# AMU-S08-V00-IDCloops.net
KiCad netlist of a schematic drawn in Altium Designer
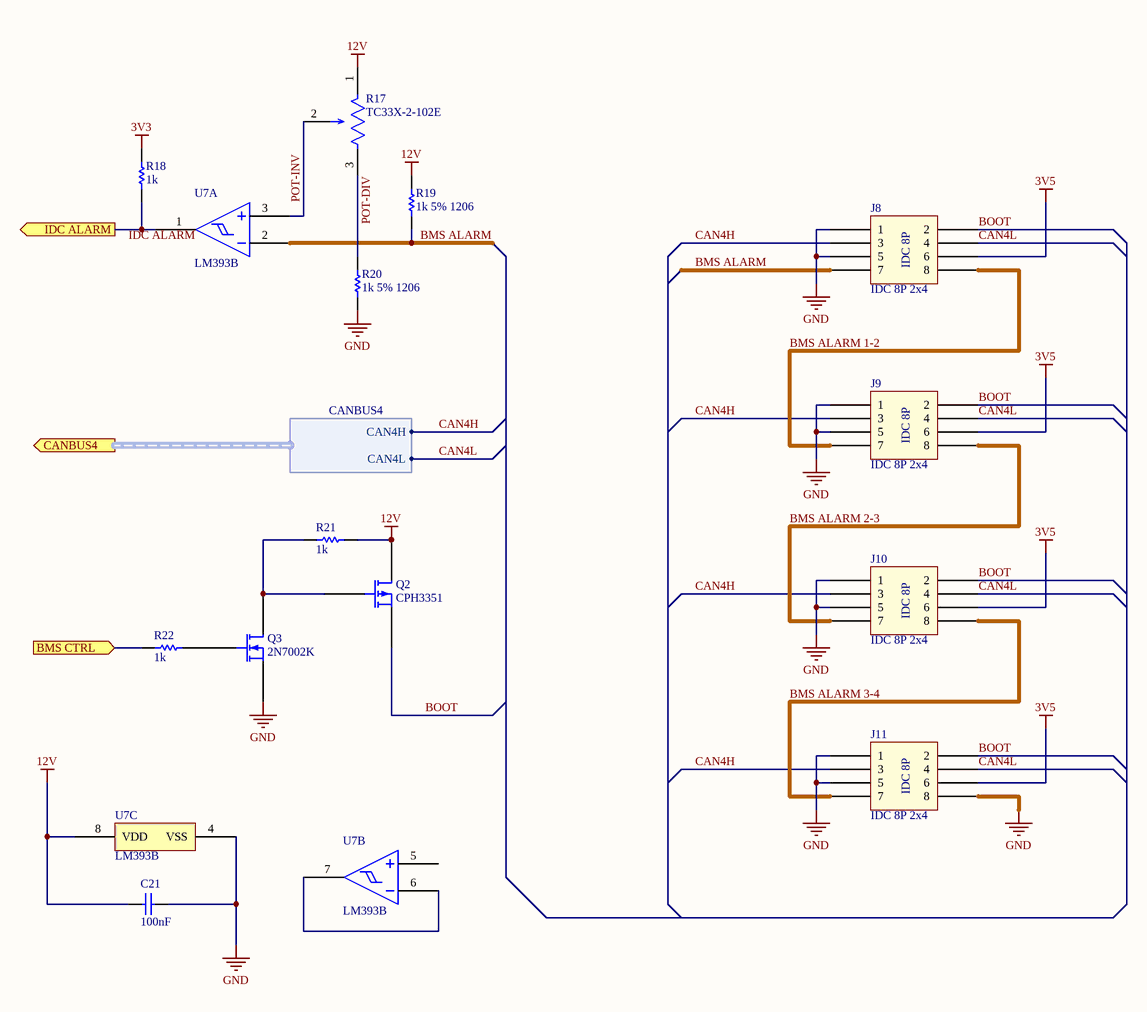
[diagram p0: AMU-S08-V00-IDCloops.SchDoc]

(export (version "E")
  (design (tool "Eeschema 10.0.6"))
  (components
    (comp (ref "C21")
      (value "100nF")
      (footprint "Cap_Ceramic_0603")
      (description "Capacitor, Ceramic, SMD, 100nF, 50V, 5%, X7R, 0603")
      (libsource (lib "StandardCapacitors") (part "100nF 50V 5% X7R 0603"))
    )
    (comp (ref "J8")
      (value "IDC 8P 2x4")
      (footprint "IDC 2.54MM 8P")
      (libsource (lib "IDCConnectors") (part "IDC 8P 2x4"))
    )
    (comp (ref "J9")
      (value "IDC 8P 2x4")
      (footprint "IDC 2.54MM 8P")
      (libsource (lib "IDCConnectors") (part "IDC 8P 2x4"))
    )
    (comp (ref "J10")
      (value "IDC 8P 2x4")
      (footprint "IDC 2.54MM 8P")
      (libsource (lib "IDCConnectors") (part "IDC 8P 2x4"))
    )
    (comp (ref "J11")
      (value "IDC 8P 2x4")
      (footprint "IDC 2.54MM 8P")
      (libsource (lib "IDCConnectors") (part "IDC 8P 2x4"))
    )
    (comp (ref "Q2")
      (value "CPH3351")
      (footprint "SOT-23-3")
      (description "P-Channel 60V 1.8A (Ta) 1W (Ta) Surface Mount 3-CPH")
      (libsource (lib "QUTMS_Transistors") (part "CPH3351"))
    )
    (comp (ref "Q3")
      (value "2N7002K")
      (footprint "SOT-23-3")
      (description "N-Channel 60V 300mA (Ta) 350mW (Ta) Surface Mount SOT-23 (TO-236AB)")
      (libsource (lib "QUTMS_Transistors") (part "2N7002K"))
    )
    (comp (ref "R17")
      (value "TC33X-2-102E")
      (footprint "TC33")
      (description "1 kOhms 0.1W, 1/10W J Lead Surface Mount Trimmer Potentiometer Cermet 1 Turn Top Adjustment")
      (libsource (lib "QUTMS_TrimmerLibrary") (part "TC33X-2-102E"))
    )
    (comp (ref "R18")
      (value "1k")
      (footprint "Res_ThinFilm_0603")
      (description "Resistor, SMD, 1k, 0.1W, 5%, 0603")
      (libsource (lib "StandardResistors") (part "1k 5% 0603"))
    )
    (comp (ref "R19")
      (value "1k 5% 1206")
      (footprint "Res_ThinFilm_1206")
      (description "1 kOhms ±5% 0.25W, 1/4W Chip Resistor 1206 (3216 Metric) Moisture Resistant Thick Film")
      (libsource (lib "StandardResistors") (part "1k 5% 1206"))
    )
    (comp (ref "R20")
      (value "1k 5% 1206")
      (footprint "Res_ThinFilm_1206")
      (description "1 kOhms ±5% 0.25W, 1/4W Chip Resistor 1206 (3216 Metric) Moisture Resistant Thick Film")
      (libsource (lib "StandardResistors") (part "1k 5% 1206"))
    )
    (comp (ref "R21")
      (value "1k")
      (footprint "Res_ThinFilm_0603")
      (description "Resistor, SMD, 1k, 0.1W, 5%, 0603")
      (libsource (lib "StandardResistors") (part "1k 5% 0603"))
    )
    (comp (ref "R22")
      (value "1k")
      (footprint "Res_ThinFilm_1206")
      (description "1 kOhms ±5% 0.25W, 1/4W Chip Resistor 1206 (3216 Metric) Moisture Resistant Thick Film")
      (libsource (lib "StandardResistors") (part "1k 5% 1206"))
    )
    (comp (ref "U7")
      (value "LM393B")
      (footprint "SOIC-8")
      (description "Comparator General Purpose Open-Collector 8-SOIC")
      (libsource (lib "QUTMS_OpAmpLibrary") (part "LM393B"))
    )
  )
  (nets
    (net (code "2") (name "/BMS ALARM") (class "Default")
      (node (ref "J8") (pin "7") (pinfunction "7_7") (pintype "passive"))
      (node (ref "R19") (pin "1") (pinfunction "1_1") (pintype "passive"))
      (node (ref "U7") (pin "2") (pinfunction "IN1-_2") (pintype "passive"))
    )
    (net (code "3") (name "/BMS ALARM 1-2") (class "Default")
      (node (ref "J8") (pin "8") (pinfunction "8_8") (pintype "passive"))
      (node (ref "J9") (pin "7") (pinfunction "7_7") (pintype "passive"))
    )
    (net (code "4") (name "/BMS ALARM 2-3") (class "Default")
      (node (ref "J10") (pin "7") (pinfunction "7_7") (pintype "passive"))
      (node (ref "J9") (pin "8") (pinfunction "8_8") (pintype "passive"))
    )
    (net (code "5") (name "/BMS ALARM 3-4") (class "Default")
      (node (ref "J10") (pin "8") (pinfunction "8_8") (pintype "passive"))
      (node (ref "J11") (pin "7") (pinfunction "7_7") (pintype "passive"))
    )
    (net (code "6") (name "/BMS CTRL") (class "Default")
      (node (ref "R22") (pin "1") (pinfunction "1_1") (pintype "passive"))
    )
    (net (code "7") (name "/BOOT") (class "Default")
      (node (ref "J10") (pin "2") (pinfunction "2_2") (pintype "passive"))
      (node (ref "J11") (pin "2") (pinfunction "2_2") (pintype "passive"))
      (node (ref "J8") (pin "2") (pinfunction "2_2") (pintype "passive"))
      (node (ref "J9") (pin "2") (pinfunction "2_2") (pintype "passive"))
      (node (ref "Q2") (pin "S") (pinfunction "S_S") (pintype "passive"))
    )
    (net (code "8") (name "/CAN4H") (class "Default")
      (node (ref "J10") (pin "3") (pinfunction "3_3") (pintype "passive"))
      (node (ref "J11") (pin "3") (pinfunction "3_3") (pintype "passive"))
      (node (ref "J8") (pin "3") (pinfunction "3_3") (pintype "passive"))
      (node (ref "J9") (pin "3") (pinfunction "3_3") (pintype "passive"))
    )
    (net (code "9") (name "/CAN4L") (class "Default")
      (node (ref "J10") (pin "4") (pinfunction "4_4") (pintype "passive"))
      (node (ref "J11") (pin "4") (pinfunction "4_4") (pintype "passive"))
      (node (ref "J8") (pin "4") (pinfunction "4_4") (pintype "passive"))
      (node (ref "J9") (pin "4") (pinfunction "4_4") (pintype "passive"))
    )
    (net (code "10") (name "/IDC ALARM") (class "Default")
      (node (ref "R18") (pin "1") (pinfunction "1_1") (pintype "passive"))
      (node (ref "U7") (pin "1") (pinfunction "OUT1_1") (pintype "passive"))
    )
    (net (code "11") (name "/POT-DIV") (class "Default")
      (node (ref "R17") (pin "3") (pinfunction "3_3") (pintype "passive"))
      (node (ref "R20") (pin "2") (pinfunction "2_2") (pintype "passive"))
    )
    (net (code "12") (name "/POT-INV") (class "Default")
      (node (ref "R17") (pin "2") (pinfunction "2_2") (pintype "passive"))
      (node (ref "U7") (pin "3") (pinfunction "IN1+_3") (pintype "passive"))
    )
    (net (code "14") (name "3V3") (class "Default")
      (node (ref "R18") (pin "2") (pinfunction "2_2") (pintype "passive"))
    )
    (net (code "15") (name "3V5") (class "Default")
      (node (ref "J10") (pin "6") (pinfunction "6_6") (pintype "passive"))
      (node (ref "J11") (pin "6") (pinfunction "6_6") (pintype "passive"))
      (node (ref "J8") (pin "6") (pinfunction "6_6") (pintype "passive"))
      (node (ref "J9") (pin "6") (pinfunction "6_6") (pintype "passive"))
    )
    (net (code "16") (name "12V") (class "Default")
      (node (ref "C21") (pin "1") (pinfunction "1_1") (pintype "passive"))
      (node (ref "Q2") (pin "D") (pinfunction "D_D") (pintype "passive"))
      (node (ref "R17") (pin "1") (pinfunction "1_1") (pintype "passive"))
      (node (ref "R19") (pin "2") (pinfunction "2_2") (pintype "passive"))
      (node (ref "R21") (pin "2") (pinfunction "2_2") (pintype "passive"))
      (node (ref "U7") (pin "8") (pinfunction "VDD_8") (pintype "passive"))
    )
    (net (code "17") (name "GND") (class "Default")
      (node (ref "C21") (pin "2") (pinfunction "2_2") (pintype "passive"))
      (node (ref "J10") (pin "1") (pinfunction "1_1") (pintype "passive"))
      (node (ref "J10") (pin "5") (pinfunction "5_5") (pintype "passive"))
      (node (ref "J11") (pin "1") (pinfunction "1_1") (pintype "passive"))
      (node (ref "J11") (pin "5") (pinfunction "5_5") (pintype "passive"))
      (node (ref "J11") (pin "8") (pinfunction "8_8") (pintype "passive"))
      (node (ref "J8") (pin "1") (pinfunction "1_1") (pintype "passive"))
      (node (ref "J8") (pin "5") (pinfunction "5_5") (pintype "passive"))
      (node (ref "J9") (pin "1") (pinfunction "1_1") (pintype "passive"))
      (node (ref "J9") (pin "5") (pinfunction "5_5") (pintype "passive"))
      (node (ref "Q3") (pin "S") (pinfunction "S_S") (pintype "passive"))
      (node (ref "R20") (pin "1") (pinfunction "1_1") (pintype "passive"))
      (node (ref "U7") (pin "4") (pinfunction "VSS_4") (pintype "passive"))
    )
    (net (code "18") (name "Net-(Q2-PadG)") (class "Default")
      (node (ref "Q2") (pin "G") (pinfunction "G_G") (pintype "passive"))
      (node (ref "Q3") (pin "D") (pinfunction "D_D") (pintype "passive"))
      (node (ref "R21") (pin "1") (pinfunction "1_1") (pintype "passive"))
    )
    (net (code "19") (name "Net-(Q3-PadG)") (class "Default")
      (node (ref "Q3") (pin "G") (pinfunction "G_G") (pintype "passive"))
      (node (ref "R22") (pin "2") (pinfunction "2_2") (pintype "passive"))
    )
    (net (code "20") (name "Net-(U7B-IN2-)") (class "Default")
      (node (ref "U7") (pin "6") (pinfunction "IN2-_6") (pintype "passive"))
      (node (ref "U7") (pin "7") (pinfunction "OUT1_7") (pintype "passive"))
    )
    (net (code "21") (name "unconnected-(U7B-IN2+-Pad5)") (class "Default")
      (node (ref "U7") (pin "5") (pinfunction "IN2+_5") (pintype "passive"))
    )
  )
)
